# WarpDrive_201811.net
KiCad netlist of a schematic drawn in EAGLE
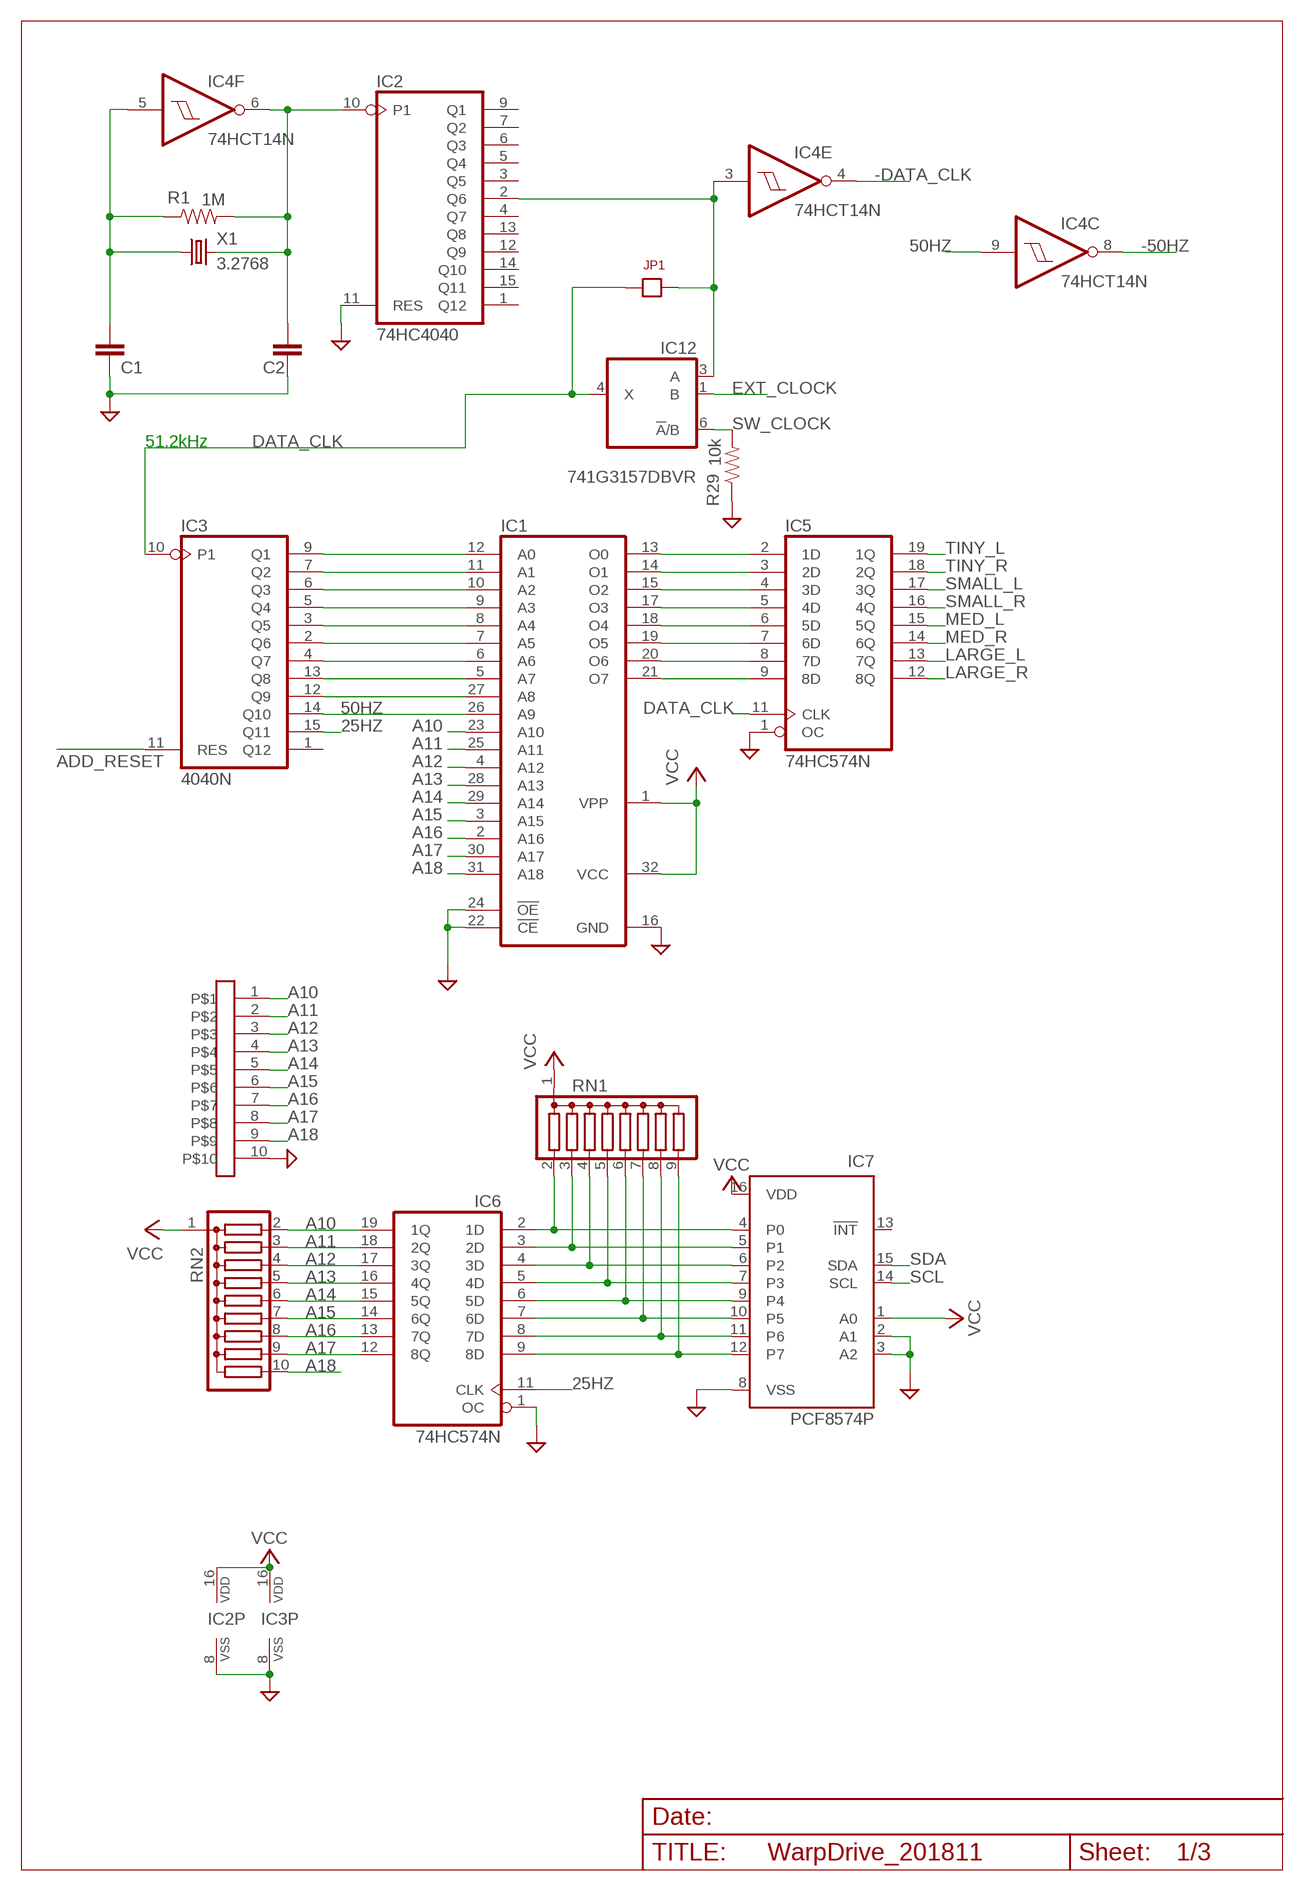
[diagram p0: schematic, sheet 1]
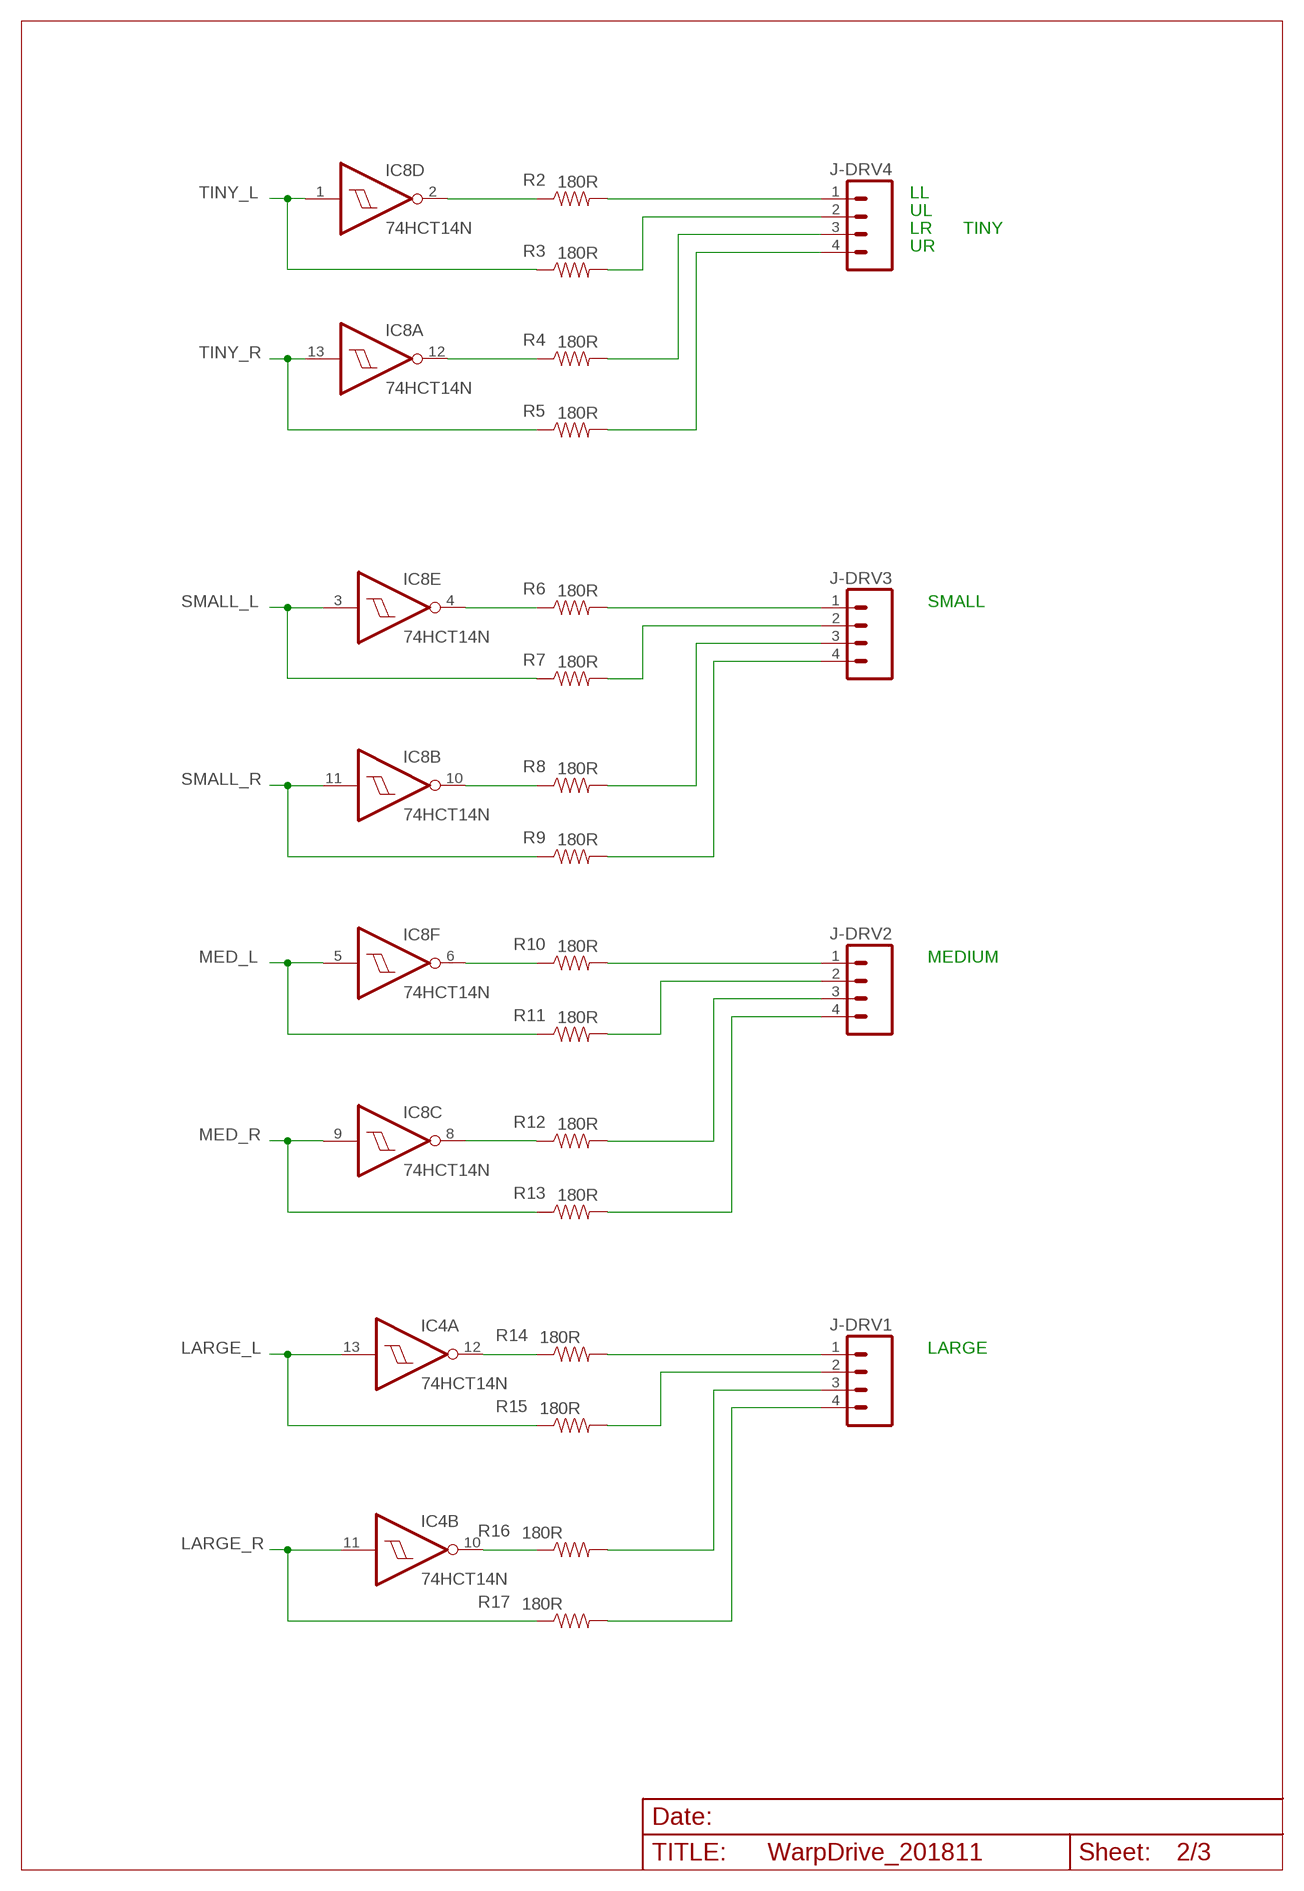
[diagram p1: schematic, sheet 2]
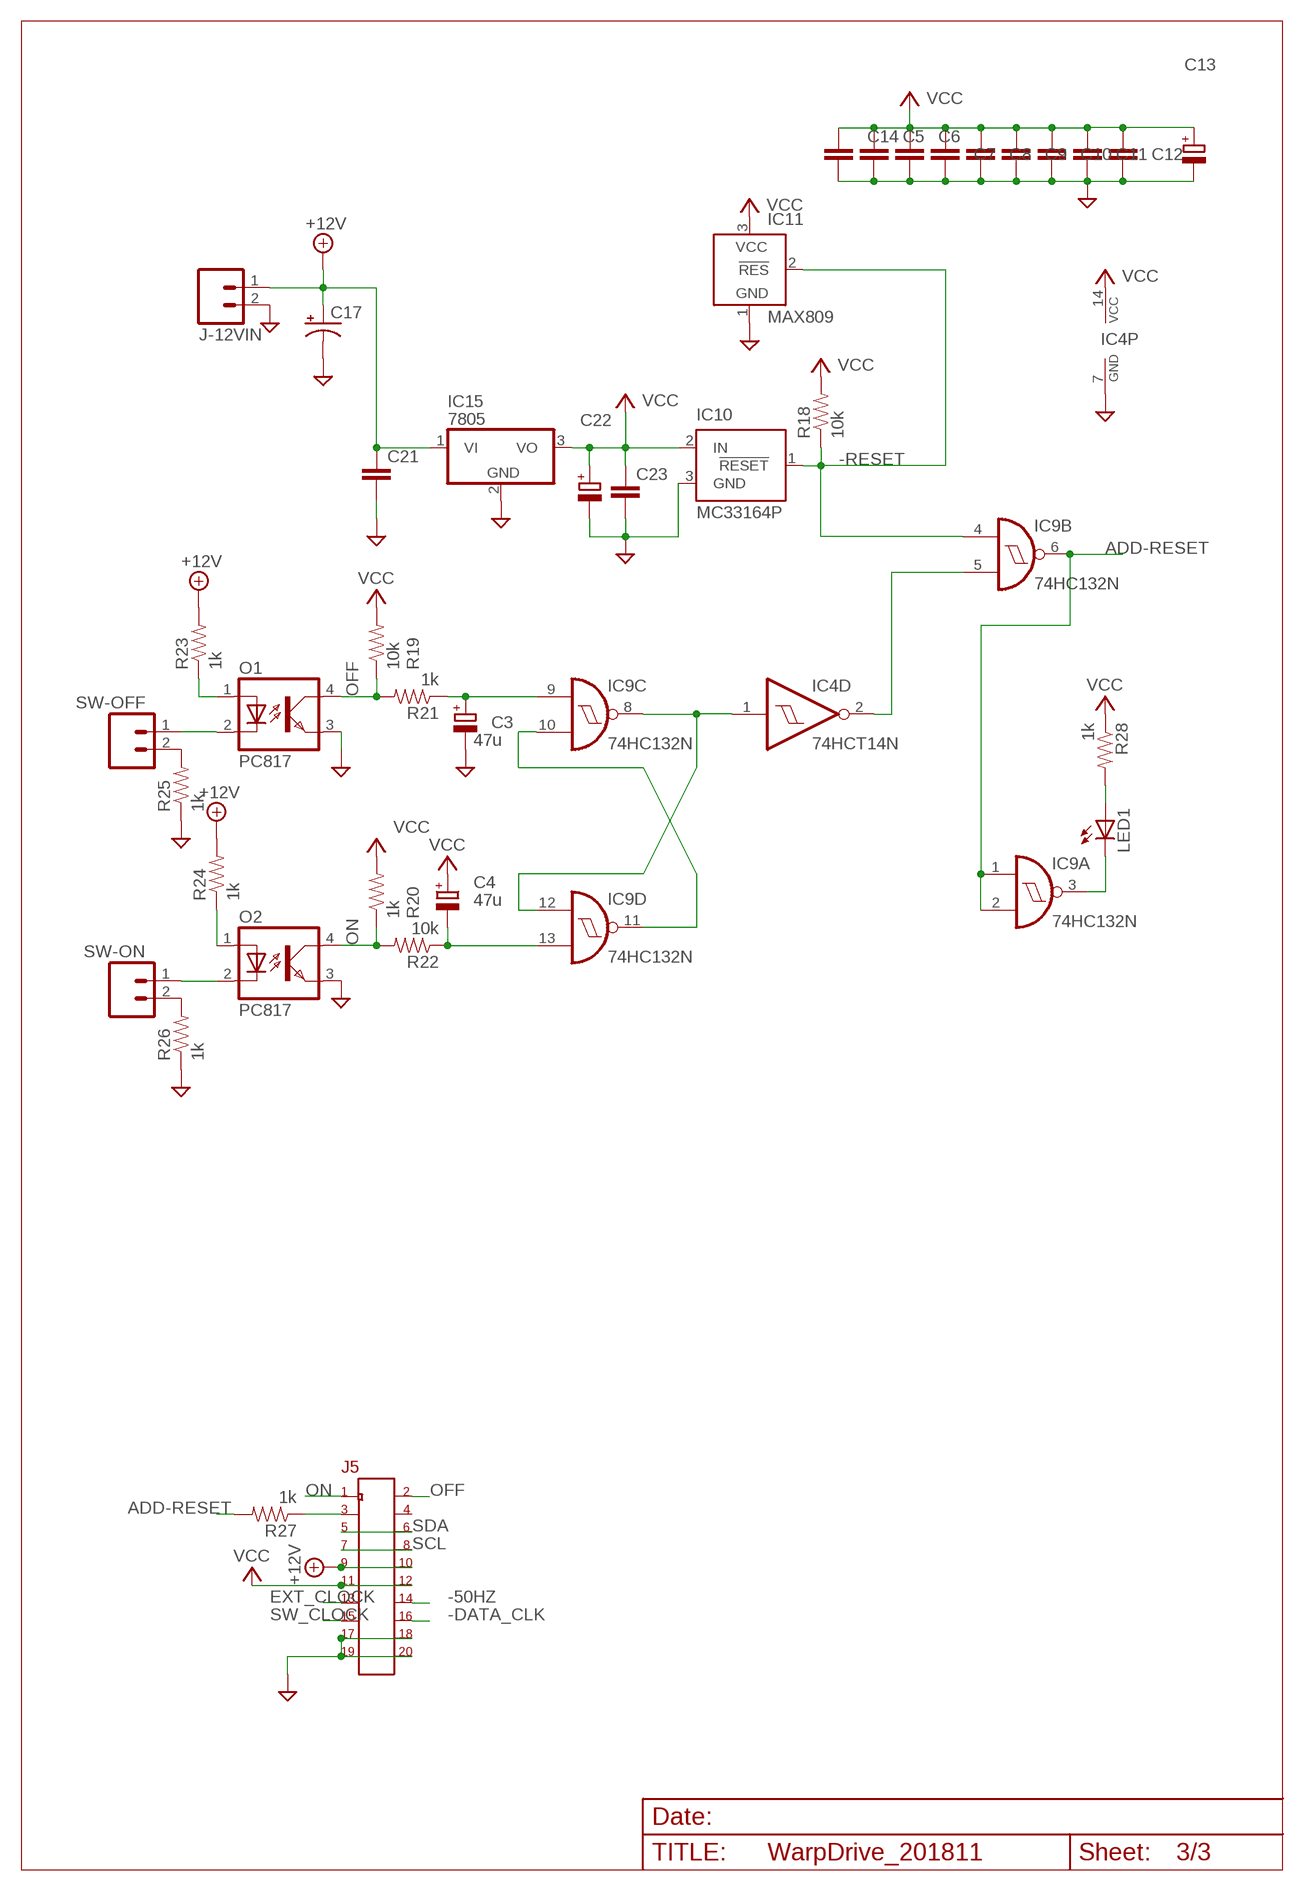
[diagram p2: schematic, sheet 3]

(export (version "E")
  (design (tool "Eeschema 10.0.6"))
  (components
    (comp (ref "C3")
      (value "47u")
      (footprint "eagle-import:CPOL-RADIAL-10UF-25V")
      (libsource (lib "eagle-import") (part "C-RB200100"))
    )
    (comp (ref "C4")
      (value "47u")
      (footprint "eagle-import:CPOL-RADIAL-10UF-25V")
      (libsource (lib "eagle-import") (part "C-RB200100"))
    )
    (comp (ref "C5")
      (value "BCAP")
      (footprint "eagle-import:BCAP")
      (libsource (lib "eagle-import") (part "BCAP"))
    )
    (comp (ref "C6")
      (value "BCAP")
      (footprint "eagle-import:BCAP")
      (libsource (lib "eagle-import") (part "BCAP"))
    )
    (comp (ref "C7")
      (value "BCAP")
      (footprint "eagle-import:BCAP")
      (libsource (lib "eagle-import") (part "BCAP"))
    )
    (comp (ref "C8")
      (value "BCAP")
      (footprint "eagle-import:BCAP")
      (libsource (lib "eagle-import") (part "BCAP"))
    )
    (comp (ref "C9")
      (value "BCAP")
      (footprint "eagle-import:BCAP")
      (libsource (lib "eagle-import") (part "BCAP"))
    )
    (comp (ref "C10")
      (value "BCAP")
      (footprint "eagle-import:BCAP")
      (libsource (lib "eagle-import") (part "BCAP"))
    )
    (comp (ref "C11")
      (value "BCAP")
      (footprint "eagle-import:BCAP")
      (libsource (lib "eagle-import") (part "BCAP"))
    )
    (comp (ref "C12")
      (value "BCAP")
      (footprint "eagle-import:BCAP")
      (libsource (lib "eagle-import") (part "BCAP"))
    )
    (comp (ref "C13")
      (value "C-RB200100")
      (footprint "eagle-import:CPOL-RADIAL-10UF-25V")
      (libsource (lib "eagle-import") (part "C-RB200100"))
    )
    (comp (ref "C14")
      (value "BCAP")
      (footprint "eagle-import:BCAP")
      (libsource (lib "eagle-import") (part "BCAP"))
    )
    (comp (ref "C17")
      (value "CAP_POLPTH1")
      (footprint "eagle-import:CPOL-RADIAL-100UF-25V")
      (libsource (lib "eagle-import") (part "CAP_POLPTH1"))
    )
    (comp (ref "C21")
      (value "BCAP")
      (footprint "eagle-import:BCAP")
      (libsource (lib "eagle-import") (part "BCAP"))
    )
    (comp (ref "C22")
      (value "C-RB200100")
      (footprint "eagle-import:CPOL-RADIAL-10UF-25V")
      (libsource (lib "eagle-import") (part "C-RB200100"))
    )
    (comp (ref "C23")
      (value "BCAP")
      (footprint "eagle-import:BCAP")
      (libsource (lib "eagle-import") (part "BCAP"))
    )
    (comp (ref "IC4")
      (value "74HCT14N")
      (footprint "eagle-import:DIL14")
      (libsource (lib "eagle-import") (part "7414NHCT"))
    )
    (comp (ref "IC9")
      (value "74HC132N")
      (footprint "eagle-import:DIL14")
      (libsource (lib "eagle-import") (part "74132NHC"))
    )
    (comp (ref "IC10")
      (value "MC33164P")
      (footprint "eagle-import:TO-226WIDE")
      (libsource (lib "eagle-import") (part "MC3164P3"))
    )
    (comp (ref "IC11")
      (value "MAX809")
      (footprint "eagle-import:SOT23B-3")
      (fields (field (name "MF") "MICROCHIP") (field (name "MPN") "TCM809MENB713"))
      (libsource (lib "eagle-import") (part "TCM809"))
    )
    (comp (ref "IC15")
      (value "7805")
      (footprint "eagle-import:TO220V")
      (libsource (lib "eagle-import") (part "78TV05"))
    )
    (comp (ref "J-12VIN")
      (value "MO2POL")
      (footprint "eagle-import:MOLEX-1X2")
      (libsource (lib "eagle-import") (part "MO2POL"))
    )
    (comp (ref "J5")
      (value "IDC20IDC20-SMALL")
      (footprint "eagle-import:IDC20-SMALL")
      (libsource (lib "eagle-import") (part "IDC20IDC20-SMALL"))
    )
    (comp (ref "LED1")
      (value "LED3MM")
      (footprint "eagle-import:LED3MM")
      (libsource (lib "eagle-import") (part "LED3MM"))
    )
    (comp (ref "O1")
      (value "PC817")
      (footprint "eagle-import:DIL04")
      (fields (field (name "MPN") "PC817X4J000F"))
      (libsource (lib "eagle-import") (part "PC817"))
    )
    (comp (ref "O2")
      (value "PC817")
      (footprint "eagle-import:DIL04")
      (fields (field (name "MPN") "PC817X4J000F"))
      (libsource (lib "eagle-import") (part "PC817"))
    )
    (comp (ref "R18")
      (value "10k")
      (footprint "eagle-import:AXIAL-0.4")
      (libsource (lib "eagle-import") (part "R4"))
    )
    (comp (ref "R19")
      (value "10k")
      (footprint "eagle-import:AXIAL-0.4")
      (libsource (lib "eagle-import") (part "R4"))
    )
    (comp (ref "R20")
      (value "1k")
      (footprint "eagle-import:AXIAL-0.4")
      (libsource (lib "eagle-import") (part "R4"))
    )
    (comp (ref "R21")
      (value "1k")
      (footprint "eagle-import:AXIAL-0.4")
      (libsource (lib "eagle-import") (part "R4"))
    )
    (comp (ref "R22")
      (value "10k")
      (footprint "eagle-import:AXIAL-0.4")
      (libsource (lib "eagle-import") (part "R4"))
    )
    (comp (ref "R23")
      (value "1k")
      (footprint "eagle-import:AXIAL-0.4")
      (libsource (lib "eagle-import") (part "R4"))
    )
    (comp (ref "R24")
      (value "1k")
      (footprint "eagle-import:AXIAL-0.4")
      (libsource (lib "eagle-import") (part "R4"))
    )
    (comp (ref "R25")
      (value "1k")
      (footprint "eagle-import:AXIAL-0.4")
      (libsource (lib "eagle-import") (part "R4"))
    )
    (comp (ref "R26")
      (value "1k")
      (footprint "eagle-import:AXIAL-0.4")
      (libsource (lib "eagle-import") (part "R4"))
    )
    (comp (ref "R27")
      (value "1k")
      (footprint "eagle-import:AXIAL-0.4")
      (libsource (lib "eagle-import") (part "R4"))
    )
    (comp (ref "R28")
      (value "1k")
      (footprint "eagle-import:AXIAL-0.4")
      (libsource (lib "eagle-import") (part "R4"))
    )
    (comp (ref "SW-OFF")
      (value "MO2POL")
      (footprint "eagle-import:MOLEX-1X2")
      (libsource (lib "eagle-import") (part "MO2POL"))
    )
    (comp (ref "SW-ON")
      (value "MO2POL")
      (footprint "eagle-import:MOLEX-1X2")
      (libsource (lib "eagle-import") (part "MO2POL"))
    )
    (comp (ref "C1")
      (value "27")
      (footprint "eagle-import:BCAP")
      (libsource (lib "eagle-import") (part "BCAP"))
    )
    (comp (ref "C2")
      (value "BCAP")
      (footprint "eagle-import:BCAP")
      (libsource (lib "eagle-import") (part "BCAP"))
    )
    (comp (ref "IC1")
      (value "27C4001D")
      (footprint "eagle-import:DIL32")
      (fields (field (name "MPN") "M27C4001-12B1"))
      (libsource (lib "eagle-import") (part "27C4001D"))
    )
    (comp (ref "IC2")
      (value "74HC4040")
      (footprint "eagle-import:DIL16")
      (libsource (lib "eagle-import") (part "4040N"))
    )
    (comp (ref "IC3")
      (value "4040N")
      (footprint "eagle-import:DIL16")
      (libsource (lib "eagle-import") (part "4040N"))
    )
    (comp (ref "IC5")
      (value "74HC574N")
      (footprint "eagle-import:DIL20")
      (libsource (lib "eagle-import") (part "74574NHC"))
    )
    (comp (ref "IC6")
      (value "74HC574N")
      (footprint "eagle-import:DIL20")
      (libsource (lib "eagle-import") (part "74574NHC"))
    )
    (comp (ref "IC7")
      (value "PCF8574P")
      (footprint "eagle-import:DIL16")
      (fields (field (name "MPN") "PCF8574PN"))
      (libsource (lib "eagle-import") (part "PCF8574P"))
    )
    (comp (ref "IC12")
      (value "741G3157DBVR")
      (footprint "eagle-import:DBV_R-PDSO-G6")
      (libsource (lib "eagle-import") (part "741G3157DBVR"))
    )
    (comp (ref "J1")
      (value "SIL-STACK-10")
      (footprint "eagle-import:SIL-STACK-10")
      (libsource (lib "eagle-import") (part "SIL-STACK-10"))
    )
    (comp (ref "JP1")
      (value "JP1")
      (footprint "eagle-import:JP1")
      (libsource (lib "eagle-import") (part "JP1"))
    )
    (comp (ref "R1")
      (value "1M")
      (footprint "eagle-import:AXIAL-0.4")
      (libsource (lib "eagle-import") (part "R4"))
    )
    (comp (ref "R29")
      (value "10k")
      (footprint "eagle-import:AXIAL-0.4")
      (libsource (lib "eagle-import") (part "R4"))
    )
    (comp (ref "RN1")
      (value "G08R")
      (footprint "eagle-import:SIL9")
      (libsource (lib "eagle-import") (part "G08R"))
    )
    (comp (ref "RN2")
      (value "G09R")
      (footprint "eagle-import:SIL10")
      (libsource (lib "eagle-import") (part "G09R"))
    )
    (comp (ref "X1")
      (value "3.2768")
      (footprint "eagle-import:HC49_S")
      (libsource (lib "eagle-import") (part "CRYSTALHC49S"))
    )
    (comp (ref "IC8")
      (value "74HCT14N")
      (footprint "eagle-import:DIL14")
      (libsource (lib "eagle-import") (part "7414NHCT"))
    )
    (comp (ref "J-DRV1")
      (value "MO4POL")
      (footprint "eagle-import:MOLEX-4")
      (libsource (lib "eagle-import") (part "MO4POL"))
    )
    (comp (ref "J-DRV2")
      (value "MO4POL")
      (footprint "eagle-import:MOLEX-4")
      (libsource (lib "eagle-import") (part "MO4POL"))
    )
    (comp (ref "J-DRV3")
      (value "MO4POL")
      (footprint "eagle-import:MOLEX-4")
      (libsource (lib "eagle-import") (part "MO4POL"))
    )
    (comp (ref "J-DRV4")
      (value "MO4POL")
      (footprint "eagle-import:MOLEX-4")
      (libsource (lib "eagle-import") (part "MO4POL"))
    )
    (comp (ref "R2")
      (value "180R")
      (footprint "eagle-import:AXIAL-0.4")
      (libsource (lib "eagle-import") (part "R4"))
    )
    (comp (ref "R3")
      (value "180R")
      (footprint "eagle-import:AXIAL-0.4")
      (libsource (lib "eagle-import") (part "R4"))
    )
    (comp (ref "R4")
      (value "180R")
      (footprint "eagle-import:AXIAL-0.4")
      (libsource (lib "eagle-import") (part "R4"))
    )
    (comp (ref "R5")
      (value "180R")
      (footprint "eagle-import:AXIAL-0.4")
      (libsource (lib "eagle-import") (part "R4"))
    )
    (comp (ref "R6")
      (value "180R")
      (footprint "eagle-import:AXIAL-0.4")
      (libsource (lib "eagle-import") (part "R4"))
    )
    (comp (ref "R7")
      (value "180R")
      (footprint "eagle-import:AXIAL-0.4")
      (libsource (lib "eagle-import") (part "R4"))
    )
    (comp (ref "R8")
      (value "180R")
      (footprint "eagle-import:AXIAL-0.4")
      (libsource (lib "eagle-import") (part "R4"))
    )
    (comp (ref "R9")
      (value "180R")
      (footprint "eagle-import:AXIAL-0.4")
      (libsource (lib "eagle-import") (part "R4"))
    )
    (comp (ref "R10")
      (value "180R")
      (footprint "eagle-import:AXIAL-0.4")
      (libsource (lib "eagle-import") (part "R4"))
    )
    (comp (ref "R11")
      (value "180R")
      (footprint "eagle-import:AXIAL-0.4")
      (libsource (lib "eagle-import") (part "R4"))
    )
    (comp (ref "R12")
      (value "180R")
      (footprint "eagle-import:AXIAL-0.4")
      (libsource (lib "eagle-import") (part "R4"))
    )
    (comp (ref "R13")
      (value "180R")
      (footprint "eagle-import:AXIAL-0.4")
      (libsource (lib "eagle-import") (part "R4"))
    )
    (comp (ref "R14")
      (value "180R")
      (footprint "eagle-import:AXIAL-0.4")
      (libsource (lib "eagle-import") (part "R4"))
    )
    (comp (ref "R15")
      (value "180R")
      (footprint "eagle-import:AXIAL-0.4")
      (libsource (lib "eagle-import") (part "R4"))
    )
    (comp (ref "R16")
      (value "180R")
      (footprint "eagle-import:AXIAL-0.4")
      (libsource (lib "eagle-import") (part "R4"))
    )
    (comp (ref "R17")
      (value "180R")
      (footprint "eagle-import:AXIAL-0.4")
      (libsource (lib "eagle-import") (part "R4"))
    )
  )
  (nets
    (net (code "1") (name "+12V") (class "Default")
      (node (ref "C17") (pin "1") (pinfunction "+_1") (pintype "passive"))
      (node (ref "C21") (pin "1") (pinfunction "1_1") (pintype "passive"))
      (node (ref "IC15") (pin "1") (pinfunction "VI_1") (pintype "input"))
      (node (ref "J-12VIN") (pin "1") (pinfunction "1_1") (pintype "passive"))
      (node (ref "J5") (pin "10") (pinfunction "10_10") (pintype "bidirectional"))
      (node (ref "J5") (pin "9") (pinfunction "9_9") (pintype "bidirectional"))
      (node (ref "R23") (pin "P$2") (pinfunction "2_P$2") (pintype "passive"))
      (node (ref "R24") (pin "P$2") (pinfunction "2_P$2") (pintype "passive"))
    )
    (net (code "2") (name "-50HZ") (class "Default")
      (node (ref "IC4") (pin "8") (pinfunction "O_8") (pintype "output"))
      (node (ref "J5") (pin "14") (pinfunction "14_14") (pintype "bidirectional"))
    )
    (net (code "3") (name "-DATA_CLK") (class "Default")
      (node (ref "IC4") (pin "4") (pinfunction "O_4") (pintype "output"))
      (node (ref "J5") (pin "16") (pinfunction "16_16") (pintype "bidirectional"))
    )
    (net (code "4") (name "-RESET") (class "Default")
      (node (ref "IC10") (pin "1") (pinfunction "~{RESET}_1") (pintype "open_collector"))
      (node (ref "IC11") (pin "2") (pinfunction "~{RES}_2") (pintype "output"))
      (node (ref "IC9") (pin "4") (pinfunction "I0_4") (pintype "input"))
      (node (ref "R18") (pin "P$1") (pinfunction "1_P$1") (pintype "passive"))
    )
    (net (code "5") (name "25HZ") (class "Default")
      (node (ref "IC3") (pin "15") (pinfunction "Q11_15") (pintype "output"))
      (node (ref "IC6") (pin "11") (pinfunction "CLK_11") (pintype "input"))
    )
    (net (code "6") (name "50HZ") (class "Default")
      (node (ref "IC1") (pin "26") (pinfunction "A9_26") (pintype "input"))
      (node (ref "IC3") (pin "14") (pinfunction "Q10_14") (pintype "output"))
      (node (ref "IC4") (pin "9") (pinfunction "I_9") (pintype "input"))
    )
    (net (code "7") (name "A10") (class "Default")
      (node (ref "IC1") (pin "23") (pinfunction "A10_23") (pintype "input"))
      (node (ref "IC6") (pin "19") (pinfunction "1Q_19") (pintype "tri_state"))
      (node (ref "J1") (pin "1") (pinfunction "P$1_1") (pintype "bidirectional"))
      (node (ref "RN2") (pin "2") (pinfunction "2_2") (pintype "passive"))
    )
    (net (code "8") (name "A11") (class "Default")
      (node (ref "IC1") (pin "25") (pinfunction "A11_25") (pintype "input"))
      (node (ref "IC6") (pin "18") (pinfunction "2Q_18") (pintype "tri_state"))
      (node (ref "J1") (pin "2") (pinfunction "P$2_2") (pintype "bidirectional"))
      (node (ref "RN2") (pin "3") (pinfunction "3_3") (pintype "passive"))
    )
    (net (code "9") (name "A12") (class "Default")
      (node (ref "IC1") (pin "4") (pinfunction "A12_4") (pintype "input"))
      (node (ref "IC6") (pin "17") (pinfunction "3Q_17") (pintype "tri_state"))
      (node (ref "J1") (pin "3") (pinfunction "P$3_3") (pintype "bidirectional"))
      (node (ref "RN2") (pin "4") (pinfunction "4_4") (pintype "passive"))
    )
    (net (code "10") (name "A13") (class "Default")
      (node (ref "IC1") (pin "28") (pinfunction "A13_28") (pintype "input"))
      (node (ref "IC6") (pin "16") (pinfunction "4Q_16") (pintype "tri_state"))
      (node (ref "J1") (pin "4") (pinfunction "P$4_4") (pintype "bidirectional"))
      (node (ref "RN2") (pin "5") (pinfunction "5_5") (pintype "passive"))
    )
    (net (code "11") (name "A14") (class "Default")
      (node (ref "IC1") (pin "29") (pinfunction "A14_29") (pintype "input"))
      (node (ref "IC6") (pin "15") (pinfunction "5Q_15") (pintype "tri_state"))
      (node (ref "J1") (pin "5") (pinfunction "P$5_5") (pintype "bidirectional"))
      (node (ref "RN2") (pin "6") (pinfunction "6_6") (pintype "passive"))
    )
    (net (code "12") (name "A15") (class "Default")
      (node (ref "IC1") (pin "3") (pinfunction "A15_3") (pintype "input"))
      (node (ref "IC6") (pin "14") (pinfunction "6Q_14") (pintype "tri_state"))
      (node (ref "J1") (pin "6") (pinfunction "P$6_6") (pintype "bidirectional"))
      (node (ref "RN2") (pin "7") (pinfunction "7_7") (pintype "passive"))
    )
    (net (code "13") (name "A16") (class "Default")
      (node (ref "IC1") (pin "2") (pinfunction "A16_2") (pintype "input"))
      (node (ref "IC6") (pin "13") (pinfunction "7Q_13") (pintype "tri_state"))
      (node (ref "J1") (pin "7") (pinfunction "P$7_7") (pintype "bidirectional"))
      (node (ref "RN2") (pin "8") (pinfunction "8_8") (pintype "passive"))
    )
    (net (code "14") (name "A17") (class "Default")
      (node (ref "IC1") (pin "30") (pinfunction "A17_30") (pintype "input"))
      (node (ref "IC6") (pin "12") (pinfunction "8Q_12") (pintype "tri_state"))
      (node (ref "J1") (pin "8") (pinfunction "P$8_8") (pintype "bidirectional"))
      (node (ref "RN2") (pin "9") (pinfunction "9_9") (pintype "passive"))
    )
    (net (code "15") (name "A18") (class "Default")
      (node (ref "IC1") (pin "31") (pinfunction "A18_31") (pintype "input"))
      (node (ref "J1") (pin "9") (pinfunction "P$9_9") (pintype "bidirectional"))
      (node (ref "RN2") (pin "10") (pinfunction "10_10") (pintype "passive"))
    )
    (net (code "16") (name "ADD-RESET") (class "Default")
      (node (ref "IC9") (pin "1") (pinfunction "I0_1") (pintype "input"))
      (node (ref "IC9") (pin "2") (pinfunction "I1_2") (pintype "input"))
      (node (ref "IC9") (pin "6") (pinfunction "O_6") (pintype "output"))
      (node (ref "R27") (pin "P$2") (pinfunction "2_P$2") (pintype "passive"))
    )
    (net (code "17") (name "ADD_RESET") (class "Default")
      (node (ref "IC3") (pin "11") (pinfunction "RES_11") (pintype "input"))
    )
    (net (code "18") (name "DATA_CLK") (class "Default")
      (node (ref "IC12") (pin "4") (pinfunction "X_4") (pintype "bidirectional"))
      (node (ref "IC3") (pin "10") (pinfunction "P1_10") (pintype "input"))
      (node (ref "IC5") (pin "11") (pinfunction "CLK_11") (pintype "input"))
      (node (ref "JP1") (pin "1") (pinfunction "1_1") (pintype "bidirectional"))
    )
    (net (code "19") (name "EXT_CLOCK") (class "Default")
      (node (ref "IC12") (pin "1") (pinfunction "B_1") (pintype "bidirectional"))
      (node (ref "J5") (pin "13") (pinfunction "13_13") (pintype "bidirectional"))
    )
    (net (code "20") (name "GND") (class "Default")
      (node (ref "C1") (pin "2") (pinfunction "2_2") (pintype "passive"))
      (node (ref "C10") (pin "2") (pinfunction "2_2") (pintype "passive"))
      (node (ref "C11") (pin "2") (pinfunction "2_2") (pintype "passive"))
      (node (ref "C12") (pin "2") (pinfunction "2_2") (pintype "passive"))
      (node (ref "C13") (pin "2") (pinfunction "-_2") (pintype "passive"))
      (node (ref "C14") (pin "2") (pinfunction "2_2") (pintype "passive"))
      (node (ref "C17") (pin "2") (pinfunction "-_2") (pintype "passive"))
      (node (ref "C2") (pin "2") (pinfunction "2_2") (pintype "passive"))
      (node (ref "C21") (pin "2") (pinfunction "2_2") (pintype "passive"))
      (node (ref "C22") (pin "2") (pinfunction "-_2") (pintype "passive"))
      (node (ref "C23") (pin "2") (pinfunction "2_2") (pintype "passive"))
      (node (ref "C3") (pin "2") (pinfunction "-_2") (pintype "passive"))
      (node (ref "C5") (pin "2") (pinfunction "2_2") (pintype "passive"))
      (node (ref "C6") (pin "2") (pinfunction "2_2") (pintype "passive"))
      (node (ref "C7") (pin "2") (pinfunction "2_2") (pintype "passive"))
      (node (ref "C8") (pin "2") (pinfunction "2_2") (pintype "passive"))
      (node (ref "C9") (pin "2") (pinfunction "2_2") (pintype "passive"))
      (node (ref "IC1") (pin "16") (pinfunction "GND_16") (pintype "power_in"))
      (node (ref "IC1") (pin "22") (pinfunction "~{CE}_22") (pintype "input"))
      (node (ref "IC1") (pin "24") (pinfunction "~{OE}_24") (pintype "input"))
      (node (ref "IC10") (pin "3") (pinfunction "GND_3") (pintype "power_in"))
      (node (ref "IC11") (pin "1") (pinfunction "GND_1") (pintype "power_in"))
      (node (ref "IC15") (pin "2") (pinfunction "GND_2") (pintype "passive"))
      (node (ref "IC2") (pin "11") (pinfunction "RES_11") (pintype "input"))
      (node (ref "IC2") (pin "8") (pinfunction "VSS_8") (pintype "power_in"))
      (node (ref "IC3") (pin "8") (pinfunction "VSS_8") (pintype "power_in"))
      (node (ref "IC4") (pin "7") (pinfunction "GND_7") (pintype "power_in"))
      (node (ref "IC5") (pin "1") (pinfunction "OC_1") (pintype "input"))
      (node (ref "IC6") (pin "1") (pinfunction "OC_1") (pintype "input"))
      (node (ref "IC7") (pin "2") (pinfunction "A1_2") (pintype "input"))
      (node (ref "IC7") (pin "3") (pinfunction "A2_3") (pintype "input"))
      (node (ref "IC7") (pin "8") (pinfunction "VSS_8") (pintype "power_in"))
      (node (ref "J-12VIN") (pin "2") (pinfunction "2_2") (pintype "passive"))
      (node (ref "J1") (pin "10") (pinfunction "P$10_10") (pintype "bidirectional"))
      (node (ref "J5") (pin "17") (pinfunction "17_17") (pintype "bidirectional"))
      (node (ref "J5") (pin "18") (pinfunction "18_18") (pintype "bidirectional"))
      (node (ref "J5") (pin "19") (pinfunction "19_19") (pintype "bidirectional"))
      (node (ref "J5") (pin "20") (pinfunction "20_20") (pintype "bidirectional"))
      (node (ref "O1") (pin "3") (pinfunction "EMIT_3") (pintype "passive"))
      (node (ref "O2") (pin "3") (pinfunction "EMIT_3") (pintype "passive"))
      (node (ref "R25") (pin "P$1") (pinfunction "1_P$1") (pintype "passive"))
      (node (ref "R26") (pin "P$1") (pinfunction "1_P$1") (pintype "passive"))
      (node (ref "R29") (pin "P$1") (pinfunction "1_P$1") (pintype "passive"))
    )
    (net (code "21") (name "LARGE_L") (class "Default")
      (node (ref "IC4") (pin "13") (pinfunction "I_13") (pintype "input"))
      (node (ref "IC5") (pin "13") (pinfunction "7Q_13") (pintype "tri_state"))
      (node (ref "R15") (pin "P$1") (pinfunction "1_P$1") (pintype "passive"))
    )
    (net (code "22") (name "LARGE_R") (class "Default")
      (node (ref "IC4") (pin "11") (pinfunction "I_11") (pintype "input"))
      (node (ref "IC5") (pin "12") (pinfunction "8Q_12") (pintype "tri_state"))
      (node (ref "R17") (pin "P$1") (pinfunction "1_P$1") (pintype "passive"))
    )
    (net (code "23") (name "MED_L") (class "Default")
      (node (ref "IC5") (pin "15") (pinfunction "5Q_15") (pintype "tri_state"))
      (node (ref "IC8") (pin "5") (pinfunction "I_5") (pintype "input"))
      (node (ref "R11") (pin "P$1") (pinfunction "1_P$1") (pintype "passive"))
    )
    (net (code "24") (name "MED_R") (class "Default")
      (node (ref "IC5") (pin "14") (pinfunction "6Q_14") (pintype "tri_state"))
      (node (ref "IC8") (pin "9") (pinfunction "I_9") (pintype "input"))
      (node (ref "R13") (pin "P$1") (pinfunction "1_P$1") (pintype "passive"))
    )
    (net (code "25") (name "Net-(C3-+)") (class "Default")
      (node (ref "C3") (pin "1") (pinfunction "+_1") (pintype "passive"))
      (node (ref "IC9") (pin "9") (pinfunction "I0_9") (pintype "input"))
      (node (ref "R21") (pin "P$1") (pinfunction "1_P$1") (pintype "passive"))
    )
    (net (code "26") (name "Net-(C4--)") (class "Default")
      (node (ref "C4") (pin "2") (pinfunction "-_2") (pintype "passive"))
      (node (ref "IC9") (pin "13") (pinfunction "I1_13") (pintype "input"))
      (node (ref "R22") (pin "P$1") (pinfunction "1_P$1") (pintype "passive"))
    )
    (net (code "27") (name "Net-(IC1-A0)") (class "Default")
      (node (ref "IC1") (pin "12") (pinfunction "A0_12") (pintype "input"))
      (node (ref "IC3") (pin "9") (pinfunction "Q1_9") (pintype "output"))
    )
    (net (code "28") (name "Net-(IC1-A1)") (class "Default")
      (node (ref "IC1") (pin "11") (pinfunction "A1_11") (pintype "input"))
      (node (ref "IC3") (pin "7") (pinfunction "Q2_7") (pintype "output"))
    )
    (net (code "29") (name "Net-(IC1-A2)") (class "Default")
      (node (ref "IC1") (pin "10") (pinfunction "A2_10") (pintype "input"))
      (node (ref "IC3") (pin "6") (pinfunction "Q3_6") (pintype "output"))
    )
    (net (code "30") (name "Net-(IC1-A3)") (class "Default")
      (node (ref "IC1") (pin "9") (pinfunction "A3_9") (pintype "input"))
      (node (ref "IC3") (pin "5") (pinfunction "Q4_5") (pintype "output"))
    )
    (net (code "31") (name "Net-(IC1-A4)") (class "Default")
      (node (ref "IC1") (pin "8") (pinfunction "A4_8") (pintype "input"))
      (node (ref "IC3") (pin "3") (pinfunction "Q5_3") (pintype "output"))
    )
    (net (code "32") (name "Net-(IC1-A5)") (class "Default")
      (node (ref "IC1") (pin "7") (pinfunction "A5_7") (pintype "input"))
      (node (ref "IC3") (pin "2") (pinfunction "Q6_2") (pintype "output"))
    )
    (net (code "33") (name "Net-(IC1-A6)") (class "Default")
      (node (ref "IC1") (pin "6") (pinfunction "A6_6") (pintype "input"))
      (node (ref "IC3") (pin "4") (pinfunction "Q7_4") (pintype "output"))
    )
    (net (code "34") (name "Net-(IC1-A7)") (class "Default")
      (node (ref "IC1") (pin "5") (pinfunction "A7_5") (pintype "input"))
      (node (ref "IC3") (pin "13") (pinfunction "Q8_13") (pintype "output"))
    )
    (net (code "35") (name "Net-(IC1-A8)") (class "Default")
      (node (ref "IC1") (pin "27") (pinfunction "A8_27") (pintype "input"))
      (node (ref "IC3") (pin "12") (pinfunction "Q9_12") (pintype "output"))
    )
    (net (code "36") (name "Net-(IC1-O0)") (class "Default")
      (node (ref "IC1") (pin "13") (pinfunction "O0_13") (pintype "tri_state"))
      (node (ref "IC5") (pin "2") (pinfunction "1D_2") (pintype "input"))
    )
    (net (code "37") (name "Net-(IC1-O1)") (class "Default")
      (node (ref "IC1") (pin "14") (pinfunction "O1_14") (pintype "tri_state"))
      (node (ref "IC5") (pin "3") (pinfunction "2D_3") (pintype "input"))
    )
    (net (code "38") (name "Net-(IC1-O2)") (class "Default")
      (node (ref "IC1") (pin "15") (pinfunction "O2_15") (pintype "tri_state"))
      (node (ref "IC5") (pin "4") (pinfunction "3D_4") (pintype "input"))
    )
    (net (code "39") (name "Net-(IC1-O3)") (class "Default")
      (node (ref "IC1") (pin "17") (pinfunction "O3_17") (pintype "tri_state"))
      (node (ref "IC5") (pin "5") (pinfunction "4D_5") (pintype "input"))
    )
    (net (code "40") (name "Net-(IC1-O4)") (class "Default")
      (node (ref "IC1") (pin "18") (pinfunction "O4_18") (pintype "tri_state"))
      (node (ref "IC5") (pin "6") (pinfunction "5D_6") (pintype "input"))
    )
    (net (code "41") (name "Net-(IC1-O5)") (class "Default")
      (node (ref "IC1") (pin "19") (pinfunction "O5_19") (pintype "tri_state"))
      (node (ref "IC5") (pin "7") (pinfunction "6D_7") (pintype "input"))
    )
    (net (code "42") (name "Net-(IC1-O6)") (class "Default")
      (node (ref "IC1") (pin "20") (pinfunction "O6_20") (pintype "tri_state"))
      (node (ref "IC5") (pin "8") (pinfunction "7D_8") (pintype "input"))
    )
    (net (code "43") (name "Net-(IC1-O7)") (class "Default")
      (node (ref "IC1") (pin "21") (pinfunction "O7_21") (pintype "tri_state"))
      (node (ref "IC5") (pin "9") (pinfunction "8D_9") (pintype "input"))
    )
    (net (code "44") (name "Net-(IC2A-P1)") (class "Default")
      (node (ref "C2") (pin "1") (pinfunction "1_1") (pintype "passive"))
      (node (ref "IC2") (pin "10") (pinfunction "P1_10") (pintype "input"))
      (node (ref "IC4") (pin "6") (pinfunction "O_6") (pintype "output"))
      (node (ref "R1") (pin "P$2") (pinfunction "2_P$2") (pintype "passive"))
      (node (ref "X1") (pin "2") (pinfunction "2_2") (pintype "passive"))
    )
    (net (code "45") (name "Net-(IC4A-O)") (class "Default")
      (node (ref "IC4") (pin "12") (pinfunction "O_12") (pintype "output"))
      (node (ref "R14") (pin "P$1") (pinfunction "1_P$1") (pintype "passive"))
    )
    (net (code "46") (name "Net-(IC4B-O)") (class "Default")
      (node (ref "IC4") (pin "10") (pinfunction "O_10") (pintype "output"))
      (node (ref "R16") (pin "P$1") (pinfunction "1_P$1") (pintype "passive"))
    )
    (net (code "47") (name "Net-(IC4D-I)") (class "Default")
      (node (ref "IC4") (pin "1") (pinfunction "I_1") (pintype "input"))
      (node (ref "IC9") (pin "12") (pinfunction "I0_12") (pintype "input"))
      (node (ref "IC9") (pin "8") (pinfunction "O_8") (pintype "output"))
    )
    (net (code "48") (name "Net-(IC4D-O)") (class "Default")
      (node (ref "IC4") (pin "2") (pinfunction "O_2") (pintype "output"))
      (node (ref "IC9") (pin "5") (pinfunction "I1_5") (pintype "input"))
    )
    (net (code "49") (name "Net-(IC4F-I)") (class "Default")
      (node (ref "C1") (pin "1") (pinfunction "1_1") (pintype "passive"))
      (node (ref "IC4") (pin "5") (pinfunction "I_5") (pintype "input"))
      (node (ref "R1") (pin "P$1") (pinfunction "1_P$1") (pintype "passive"))
      (node (ref "X1") (pin "1") (pinfunction "1_1") (pintype "passive"))
    )
    (net (code "50") (name "Net-(IC6A-1D)") (class "Default")
      (node (ref "IC6") (pin "2") (pinfunction "1D_2") (pintype "input"))
      (node (ref "IC7") (pin "4") (pinfunction "P0_4") (pintype "bidirectional"))
      (node (ref "RN1") (pin "2") (pinfunction "2_2") (pintype "passive"))
    )
    (net (code "51") (name "Net-(IC6A-2D)") (class "Default")
      (node (ref "IC6") (pin "3") (pinfunction "2D_3") (pintype "input"))
      (node (ref "IC7") (pin "5") (pinfunction "P1_5") (pintype "bidirectional"))
      (node (ref "RN1") (pin "3") (pinfunction "3_3") (pintype "passive"))
    )
    (net (code "52") (name "Net-(IC6A-3D)") (class "Default")
      (node (ref "IC6") (pin "4") (pinfunction "3D_4") (pintype "input"))
      (node (ref "IC7") (pin "6") (pinfunction "P2_6") (pintype "bidirectional"))
      (node (ref "RN1") (pin "4") (pinfunction "4_4") (pintype "passive"))
    )
    (net (code "53") (name "Net-(IC6A-4D)") (class "Default")
      (node (ref "IC6") (pin "5") (pinfunction "4D_5") (pintype "input"))
      (node (ref "IC7") (pin "7") (pinfunction "P3_7") (pintype "bidirectional"))
      (node (ref "RN1") (pin "5") (pinfunction "5_5") (pintype "passive"))
    )
    (net (code "54") (name "Net-(IC6A-5D)") (class "Default")
      (node (ref "IC6") (pin "6") (pinfunction "5D_6") (pintype "input"))
      (node (ref "IC7") (pin "9") (pinfunction "P4_9") (pintype "bidirectional"))
      (node (ref "RN1") (pin "6") (pinfunction "6_6") (pintype "passive"))
    )
    (net (code "55") (name "Net-(IC6A-6D)") (class "Default")
      (node (ref "IC6") (pin "7") (pinfunction "6D_7") (pintype "input"))
      (node (ref "IC7") (pin "10") (pinfunction "P5_10") (pintype "bidirectional"))
      (node (ref "RN1") (pin "7") (pinfunction "7_7") (pintype "passive"))
    )
    (net (code "56") (name "Net-(IC6A-7D)") (class "Default")
      (node (ref "IC6") (pin "8") (pinfunction "7D_8") (pintype "input"))
      (node (ref "IC7") (pin "11") (pinfunction "P6_11") (pintype "bidirectional"))
      (node (ref "RN1") (pin "8") (pinfunction "8_8") (pintype "passive"))
    )
    (net (code "57") (name "Net-(IC6A-8D)") (class "Default")
      (node (ref "IC6") (pin "9") (pinfunction "8D_9") (pintype "input"))
      (node (ref "IC7") (pin "12") (pinfunction "P7_12") (pintype "bidirectional"))
      (node (ref "RN1") (pin "9") (pinfunction "9_9") (pintype "passive"))
    )
    (net (code "58") (name "Net-(IC8A-O)") (class "Default")
      (node (ref "IC8") (pin "12") (pinfunction "O_12") (pintype "output"))
      (node (ref "R4") (pin "P$1") (pinfunction "1_P$1") (pintype "passive"))
    )
    (net (code "59") (name "Net-(IC8B-O)") (class "Default")
      (node (ref "IC8") (pin "10") (pinfunction "O_10") (pintype "output"))
      (node (ref "R8") (pin "P$1") (pinfunction "1_P$1") (pintype "passive"))
    )
    (net (code "60") (name "Net-(IC8C-O)") (class "Default")
      (node (ref "IC8") (pin "8") (pinfunction "O_8") (pintype "output"))
      (node (ref "R12") (pin "P$1") (pinfunction "1_P$1") (pintype "passive"))
    )
    (net (code "61") (name "Net-(IC8D-O)") (class "Default")
      (node (ref "IC8") (pin "2") (pinfunction "O_2") (pintype "output"))
      (node (ref "R2") (pin "P$1") (pinfunction "1_P$1") (pintype "passive"))
    )
    (net (code "62") (name "Net-(IC8E-O)") (class "Default")
      (node (ref "IC8") (pin "4") (pinfunction "O_4") (pintype "output"))
      (node (ref "R6") (pin "P$1") (pinfunction "1_P$1") (pintype "passive"))
    )
    (net (code "63") (name "Net-(IC8F-O)") (class "Default")
      (node (ref "IC8") (pin "6") (pinfunction "O_6") (pintype "output"))
      (node (ref "R10") (pin "P$1") (pinfunction "1_P$1") (pintype "passive"))
    )
    (net (code "64") (name "Net-(IC9A-O)") (class "Default")
      (node (ref "IC9") (pin "3") (pinfunction "O_3") (pintype "output"))
      (node (ref "LED1") (pin "K") (pinfunction "C_K") (pintype "passive"))
    )
    (net (code "65") (name "Net-(IC9C-I1)") (class "Default")
      (node (ref "IC9") (pin "10") (pinfunction "I1_10") (pintype "input"))
      (node (ref "IC9") (pin "11") (pinfunction "O_11") (pintype "output"))
    )
    (net (code "66") (name "Net-(IC12A-A)") (class "Default")
      (node (ref "IC12") (pin "3") (pinfunction "A_3") (pintype "bidirectional"))
      (node (ref "IC2") (pin "2") (pinfunction "Q6_2") (pintype "output"))
      (node (ref "IC4") (pin "3") (pinfunction "I_3") (pintype "input"))
      (node (ref "JP1") (pin "2") (pinfunction "2_2") (pintype "bidirectional"))
    )
    (net (code "67") (name "Net-(O1-A)") (class "Default")
      (node (ref "O1") (pin "1") (pinfunction "A_1") (pintype "passive"))
      (node (ref "R23") (pin "P$1") (pinfunction "1_P$1") (pintype "passive"))
    )
    (net (code "68") (name "Net-(O1-C)") (class "Default")
      (node (ref "O1") (pin "2") (pinfunction "C_2") (pintype "passive"))
      (node (ref "SW-OFF") (pin "1") (pinfunction "1_1") (pintype "passive"))
    )
    (net (code "69") (name "Net-(O2-A)") (class "Default")
      (node (ref "O2") (pin "1") (pinfunction "A_1") (pintype "passive"))
      (node (ref "R24") (pin "P$1") (pinfunction "1_P$1") (pintype "passive"))
    )
    (net (code "70") (name "Net-(O2-C)") (class "Default")
      (node (ref "O2") (pin "2") (pinfunction "C_2") (pintype "passive"))
      (node (ref "SW-ON") (pin "1") (pinfunction "1_1") (pintype "passive"))
    )
    (net (code "71") (name "Net-(R2-2)") (class "Default")
      (node (ref "J-DRV4") (pin "1") (pinfunction "1_1") (pintype "passive"))
      (node (ref "R2") (pin "P$2") (pinfunction "2_P$2") (pintype "passive"))
    )
    (net (code "72") (name "Net-(R3-2)") (class "Default")
      (node (ref "J-DRV4") (pin "2") (pinfunction "2_2") (pintype "passive"))
      (node (ref "R3") (pin "P$2") (pinfunction "2_P$2") (pintype "passive"))
    )
    (net (code "73") (name "Net-(R4-2)") (class "Default")
      (node (ref "J-DRV4") (pin "3") (pinfunction "3_3") (pintype "passive"))
      (node (ref "R4") (pin "P$2") (pinfunction "2_P$2") (pintype "passive"))
    )
    (net (code "74") (name "Net-(R5-2)") (class "Default")
      (node (ref "J-DRV4") (pin "4") (pinfunction "4_4") (pintype "passive"))
      (node (ref "R5") (pin "P$2") (pinfunction "2_P$2") (pintype "passive"))
    )
    (net (code "75") (name "Net-(R6-2)") (class "Default")
      (node (ref "J-DRV3") (pin "1") (pinfunction "1_1") (pintype "passive"))
      (node (ref "R6") (pin "P$2") (pinfunction "2_P$2") (pintype "passive"))
    )
    (net (code "76") (name "Net-(R7-2)") (class "Default")
      (node (ref "J-DRV3") (pin "2") (pinfunction "2_2") (pintype "passive"))
      (node (ref "R7") (pin "P$2") (pinfunction "2_P$2") (pintype "passive"))
    )
    (net (code "77") (name "Net-(R8-2)") (class "Default")
      (node (ref "J-DRV3") (pin "3") (pinfunction "3_3") (pintype "passive"))
      (node (ref "R8") (pin "P$2") (pinfunction "2_P$2") (pintype "passive"))
    )
    (net (code "78") (name "Net-(R9-2)") (class "Default")
      (node (ref "J-DRV3") (pin "4") (pinfunction "4_4") (pintype "passive"))
      (node (ref "R9") (pin "P$2") (pinfunction "2_P$2") (pintype "passive"))
    )
    (net (code "79") (name "Net-(R10-2)") (class "Default")
      (node (ref "J-DRV2") (pin "1") (pinfunction "1_1") (pintype "passive"))
      (node (ref "R10") (pin "P$2") (pinfunction "2_P$2") (pintype "passive"))
    )
    (net (code "80") (name "Net-(R11-2)") (class "Default")
      (node (ref "J-DRV2") (pin "2") (pinfunction "2_2") (pintype "passive"))
      (node (ref "R11") (pin "P$2") (pinfunction "2_P$2") (pintype "passive"))
    )
    (net (code "81") (name "Net-(R12-2)") (class "Default")
      (node (ref "J-DRV2") (pin "3") (pinfunction "3_3") (pintype "passive"))
      (node (ref "R12") (pin "P$2") (pinfunction "2_P$2") (pintype "passive"))
    )
    (net (code "82") (name "Net-(R13-2)") (class "Default")
      (node (ref "J-DRV2") (pin "4") (pinfunction "4_4") (pintype "passive"))
      (node (ref "R13") (pin "P$2") (pinfunction "2_P$2") (pintype "passive"))
    )
    (net (code "83") (name "Net-(R14-2)") (class "Default")
      (node (ref "J-DRV1") (pin "1") (pinfunction "1_1") (pintype "passive"))
      (node (ref "R14") (pin "P$2") (pinfunction "2_P$2") (pintype "passive"))
    )
    (net (code "84") (name "Net-(R15-2)") (class "Default")
      (node (ref "J-DRV1") (pin "2") (pinfunction "2_2") (pintype "passive"))
      (node (ref "R15") (pin "P$2") (pinfunction "2_P$2") (pintype "passive"))
    )
    (net (code "85") (name "Net-(R16-2)") (class "Default")
      (node (ref "J-DRV1") (pin "3") (pinfunction "3_3") (pintype "passive"))
      (node (ref "R16") (pin "P$2") (pinfunction "2_P$2") (pintype "passive"))
    )
    (net (code "86") (name "Net-(R17-2)") (class "Default")
      (node (ref "J-DRV1") (pin "4") (pinfunction "4_4") (pintype "passive"))
      (node (ref "R17") (pin "P$2") (pinfunction "2_P$2") (pintype "passive"))
    )
    (net (code "87") (name "Net-(R25-2)") (class "Default")
      (node (ref "R25") (pin "P$2") (pinfunction "2_P$2") (pintype "passive"))
      (node (ref "SW-OFF") (pin "2") (pinfunction "2_2") (pintype "passive"))
    )
    (net (code "88") (name "Net-(R26-2)") (class "Default")
      (node (ref "R26") (pin "P$2") (pinfunction "2_P$2") (pintype "passive"))
      (node (ref "SW-ON") (pin "2") (pinfunction "2_2") (pintype "passive"))
    )
    (net (code "89") (name "Net-(R27-1)") (class "Default")
      (node (ref "J5") (pin "3") (pinfunction "3_3") (pintype "bidirectional"))
      (node (ref "R27") (pin "P$1") (pinfunction "1_P$1") (pintype "passive"))
    )
    (net (code "90") (name "Net-(R28-2)") (class "Default")
      (node (ref "LED1") (pin "A") (pinfunction "A_A") (pintype "passive"))
      (node (ref "R28") (pin "P$2") (pinfunction "2_P$2") (pintype "passive"))
    )
    (net (code "91") (name "OFF") (class "Default")
      (node (ref "J5") (pin "2") (pinfunction "2_2") (pintype "bidirectional"))
      (node (ref "O1") (pin "4") (pinfunction "COL_4") (pintype "passive"))
      (node (ref "R19") (pin "P$1") (pinfunction "1_P$1") (pintype "passive"))
      (node (ref "R21") (pin "P$2") (pinfunction "2_P$2") (pintype "passive"))
    )
    (net (code "92") (name "ON") (class "Default")
      (node (ref "J5") (pin "1") (pinfunction "1_1") (pintype "bidirectional"))
      (node (ref "O2") (pin "4") (pinfunction "COL_4") (pintype "passive"))
      (node (ref "R20") (pin "P$1") (pinfunction "1_P$1") (pintype "passive"))
      (node (ref "R22") (pin "P$2") (pinfunction "2_P$2") (pintype "passive"))
    )
    (net (code "93") (name "SCL") (class "Default")
      (node (ref "IC7") (pin "14") (pinfunction "SCL_14") (pintype "input"))
      (node (ref "J5") (pin "7") (pinfunction "7_7") (pintype "bidirectional"))
      (node (ref "J5") (pin "8") (pinfunction "8_8") (pintype "bidirectional"))
    )
    (net (code "94") (name "SDA") (class "Default")
      (node (ref "IC7") (pin "15") (pinfunction "SDA_15") (pintype "bidirectional"))
      (node (ref "J5") (pin "5") (pinfunction "5_5") (pintype "bidirectional"))
      (node (ref "J5") (pin "6") (pinfunction "6_6") (pintype "bidirectional"))
    )
    (net (code "95") (name "SMALL_L") (class "Default")
      (node (ref "IC5") (pin "17") (pinfunction "3Q_17") (pintype "tri_state"))
      (node (ref "IC8") (pin "3") (pinfunction "I_3") (pintype "input"))
      (node (ref "R7") (pin "P$1") (pinfunction "1_P$1") (pintype "passive"))
    )
    (net (code "96") (name "SMALL_R") (class "Default")
      (node (ref "IC5") (pin "16") (pinfunction "4Q_16") (pintype "tri_state"))
      (node (ref "IC8") (pin "11") (pinfunction "I_11") (pintype "input"))
      (node (ref "R9") (pin "P$1") (pinfunction "1_P$1") (pintype "passive"))
    )
    (net (code "97") (name "SW_CLOCK") (class "Default")
      (node (ref "IC12") (pin "6") (pinfunction "~{A}/B_6") (pintype "input"))
      (node (ref "J5") (pin "15") (pinfunction "15_15") (pintype "bidirectional"))
      (node (ref "R29") (pin "P$2") (pinfunction "2_P$2") (pintype "passive"))
    )
    (net (code "98") (name "TINY_L") (class "Default")
      (node (ref "IC5") (pin "19") (pinfunction "1Q_19") (pintype "tri_state"))
      (node (ref "IC8") (pin "1") (pinfunction "I_1") (pintype "input"))
      (node (ref "R3") (pin "P$1") (pinfunction "1_P$1") (pintype "passive"))
    )
    (net (code "99") (name "TINY_R") (class "Default")
      (node (ref "IC5") (pin "18") (pinfunction "2Q_18") (pintype "tri_state"))
      (node (ref "IC8") (pin "13") (pinfunction "I_13") (pintype "input"))
      (node (ref "R5") (pin "P$1") (pinfunction "1_P$1") (pintype "passive"))
    )
    (net (code "100") (name "VCC") (class "Default")
      (node (ref "C10") (pin "1") (pinfunction "1_1") (pintype "passive"))
      (node (ref "C11") (pin "1") (pinfunction "1_1") (pintype "passive"))
      (node (ref "C12") (pin "1") (pinfunction "1_1") (pintype "passive"))
      (node (ref "C13") (pin "1") (pinfunction "+_1") (pintype "passive"))
      (node (ref "C14") (pin "1") (pinfunction "1_1") (pintype "passive"))
      (node (ref "C22") (pin "1") (pinfunction "+_1") (pintype "passive"))
      (node (ref "C23") (pin "1") (pinfunction "1_1") (pintype "passive"))
      (node (ref "C4") (pin "1") (pinfunction "+_1") (pintype "passive"))
      (node (ref "C5") (pin "1") (pinfunction "1_1") (pintype "passive"))
      (node (ref "C6") (pin "1") (pinfunction "1_1") (pintype "passive"))
      (node (ref "C7") (pin "1") (pinfunction "1_1") (pintype "passive"))
      (node (ref "C8") (pin "1") (pinfunction "1_1") (pintype "passive"))
      (node (ref "C9") (pin "1") (pinfunction "1_1") (pintype "passive"))
      (node (ref "IC1") (pin "1") (pinfunction "VPP_1") (pintype "passive"))
      (node (ref "IC1") (pin "32") (pinfunction "VCC_32") (pintype "power_in"))
      (node (ref "IC10") (pin "2") (pinfunction "IN_2") (pintype "input"))
      (node (ref "IC11") (pin "3") (pinfunction "VCC_3") (pintype "power_in"))
      (node (ref "IC15") (pin "3") (pinfunction "VO_3") (pintype "passive"))
      (node (ref "IC2") (pin "16") (pinfunction "VDD_16") (pintype "power_in"))
      (node (ref "IC3") (pin "16") (pinfunction "VDD_16") (pintype "power_in"))
      (node (ref "IC4") (pin "14") (pinfunction "VCC_14") (pintype "power_in"))
      (node (ref "IC7") (pin "1") (pinfunction "A0_1") (pintype "input"))
      (node (ref "IC7") (pin "16") (pinfunction "VDD_16") (pintype "power_in"))
      (node (ref "J5") (pin "11") (pinfunction "11_11") (pintype "bidirectional"))
      (node (ref "J5") (pin "12") (pinfunction "12_12") (pintype "bidirectional"))
      (node (ref "R18") (pin "P$2") (pinfunction "2_P$2") (pintype "passive"))
      (node (ref "R19") (pin "P$2") (pinfunction "2_P$2") (pintype "passive"))
      (node (ref "R20") (pin "P$2") (pinfunction "2_P$2") (pintype "passive"))
      (node (ref "R28") (pin "P$1") (pinfunction "1_P$1") (pintype "passive"))
      (node (ref "RN1") (pin "1") (pinfunction "1_1") (pintype "passive"))
      (node (ref "RN2") (pin "1") (pinfunction "1_1") (pintype "passive"))
    )
    (net (code "101") (name "unconnected-(IC2A-Q1-Pad9)") (class "Default")
      (node (ref "IC2") (pin "9") (pinfunction "Q1_9") (pintype "output"))
    )
    (net (code "102") (name "unconnected-(IC2A-Q2-Pad7)") (class "Default")
      (node (ref "IC2") (pin "7") (pinfunction "Q2_7") (pintype "output"))
    )
    (net (code "103") (name "unconnected-(IC2A-Q3-Pad6)") (class "Default")
      (node (ref "IC2") (pin "6") (pinfunction "Q3_6") (pintype "output"))
    )
    (net (code "104") (name "unconnected-(IC2A-Q4-Pad5)") (class "Default")
      (node (ref "IC2") (pin "5") (pinfunction "Q4_5") (pintype "output"))
    )
    (net (code "105") (name "unconnected-(IC2A-Q5-Pad3)") (class "Default")
      (node (ref "IC2") (pin "3") (pinfunction "Q5_3") (pintype "output"))
    )
    (net (code "106") (name "unconnected-(IC2A-Q7-Pad4)") (class "Default")
      (node (ref "IC2") (pin "4") (pinfunction "Q7_4") (pintype "output"))
    )
    (net (code "107") (name "unconnected-(IC2A-Q8-Pad13)") (class "Default")
      (node (ref "IC2") (pin "13") (pinfunction "Q8_13") (pintype "output"))
    )
    (net (code "108") (name "unconnected-(IC2A-Q9-Pad12)") (class "Default")
      (node (ref "IC2") (pin "12") (pinfunction "Q9_12") (pintype "output"))
    )
    (net (code "109") (name "unconnected-(IC2A-Q10-Pad14)") (class "Default")
      (node (ref "IC2") (pin "14") (pinfunction "Q10_14") (pintype "output"))
    )
    (net (code "110") (name "unconnected-(IC2A-Q11-Pad15)") (class "Default")
      (node (ref "IC2") (pin "15") (pinfunction "Q11_15") (pintype "output"))
    )
    (net (code "111") (name "unconnected-(IC2A-Q12-Pad1)") (class "Default")
      (node (ref "IC2") (pin "1") (pinfunction "Q12_1") (pintype "output"))
    )
    (net (code "112") (name "unconnected-(IC3A-Q12-Pad1)") (class "Default")
      (node (ref "IC3") (pin "1") (pinfunction "Q12_1") (pintype "output"))
    )
    (net (code "113") (name "unconnected-(IC7-~{INT}-Pad13)") (class "Default")
      (node (ref "IC7") (pin "13") (pinfunction "~{INT}_13") (pintype "output"))
    )
    (net (code "114") (name "unconnected-(J5-Pad4)") (class "Default")
      (node (ref "J5") (pin "4") (pinfunction "4_4") (pintype "bidirectional"))
    )
  )
)
